# ReSpeaker_Mic_SMD25_V04.net
KiCad netlist of a schematic drawn in EAGLE
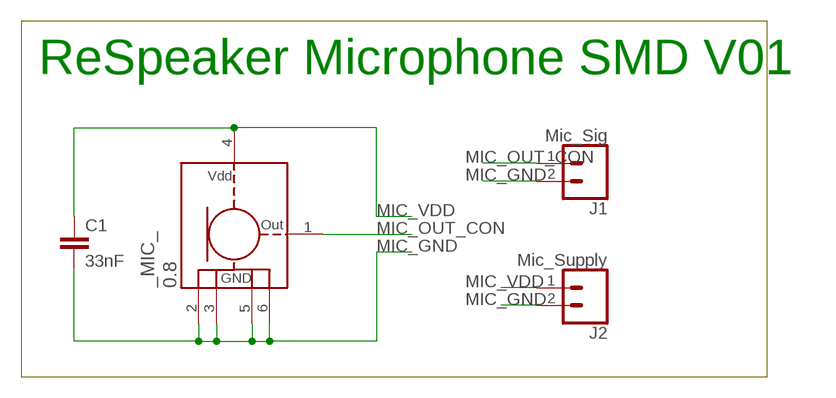
[diagram p0: schematic, sheet 1]

(export (version "E")
  (design (tool "Eeschema 10.0.6"))
  (components
    (comp (ref "C1")
      (value "33nF")
      (footprint "eagle-import:0805")
      (libsource (lib "eagle-import") (part "1.0UF-0805-25V-10%"))
    )
    (comp (ref "J1")
      (value "Mic_Sig")
      (footprint "eagle-import:1X02")
      (libsource (lib "eagle-import") (part "CONN_02"))
    )
    (comp (ref "J2")
      (value "Mic_Supply")
      (footprint "eagle-import:1X02")
      (libsource (lib "eagle-import") (part "CONN_02"))
    )
    (comp (ref "_MIC_")
      (value "0.8")
      (footprint "eagle-import:SPU0410LR5H-QB_0.8")
      (libsource (lib "eagle-import") (part "SPU0410LR5H-QBSPU0410LR5H-QB_0.8"))
    )
  )
  (nets
    (net (code "1") (name "/MIC_GND") (class "Default")
      (node (ref "C1") (pin "2") (pinfunction "2_2") (pintype "passive"))
      (node (ref "J1") (pin "2") (pinfunction "2_2") (pintype "passive"))
      (node (ref "J2") (pin "2") (pinfunction "2_2") (pintype "passive"))
      (node (ref "_MIC_") (pin "2") (pinfunction "GND_2") (pintype "bidirectional"))
      (node (ref "_MIC_") (pin "3") (pinfunction "GND_3") (pintype "bidirectional"))
      (node (ref "_MIC_") (pin "5") (pinfunction "GND_5") (pintype "bidirectional"))
      (node (ref "_MIC_") (pin "6") (pinfunction "GND_6") (pintype "bidirectional"))
    )
    (net (code "2") (name "/MIC_OUT_CON") (class "Default")
      (node (ref "J1") (pin "1") (pinfunction "1_1") (pintype "passive"))
      (node (ref "_MIC_") (pin "1") (pinfunction "OUT_1") (pintype "bidirectional"))
    )
    (net (code "3") (name "/MIC_VDD") (class "Default")
      (node (ref "C1") (pin "1") (pinfunction "1_1") (pintype "passive"))
      (node (ref "J2") (pin "1") (pinfunction "1_1") (pintype "passive"))
      (node (ref "_MIC_") (pin "4") (pinfunction "VDD_4") (pintype "bidirectional"))
    )
  )
)
